# Cansat2019_1516_Container_v04.net
KiCad netlist of a schematic drawn in EAGLE
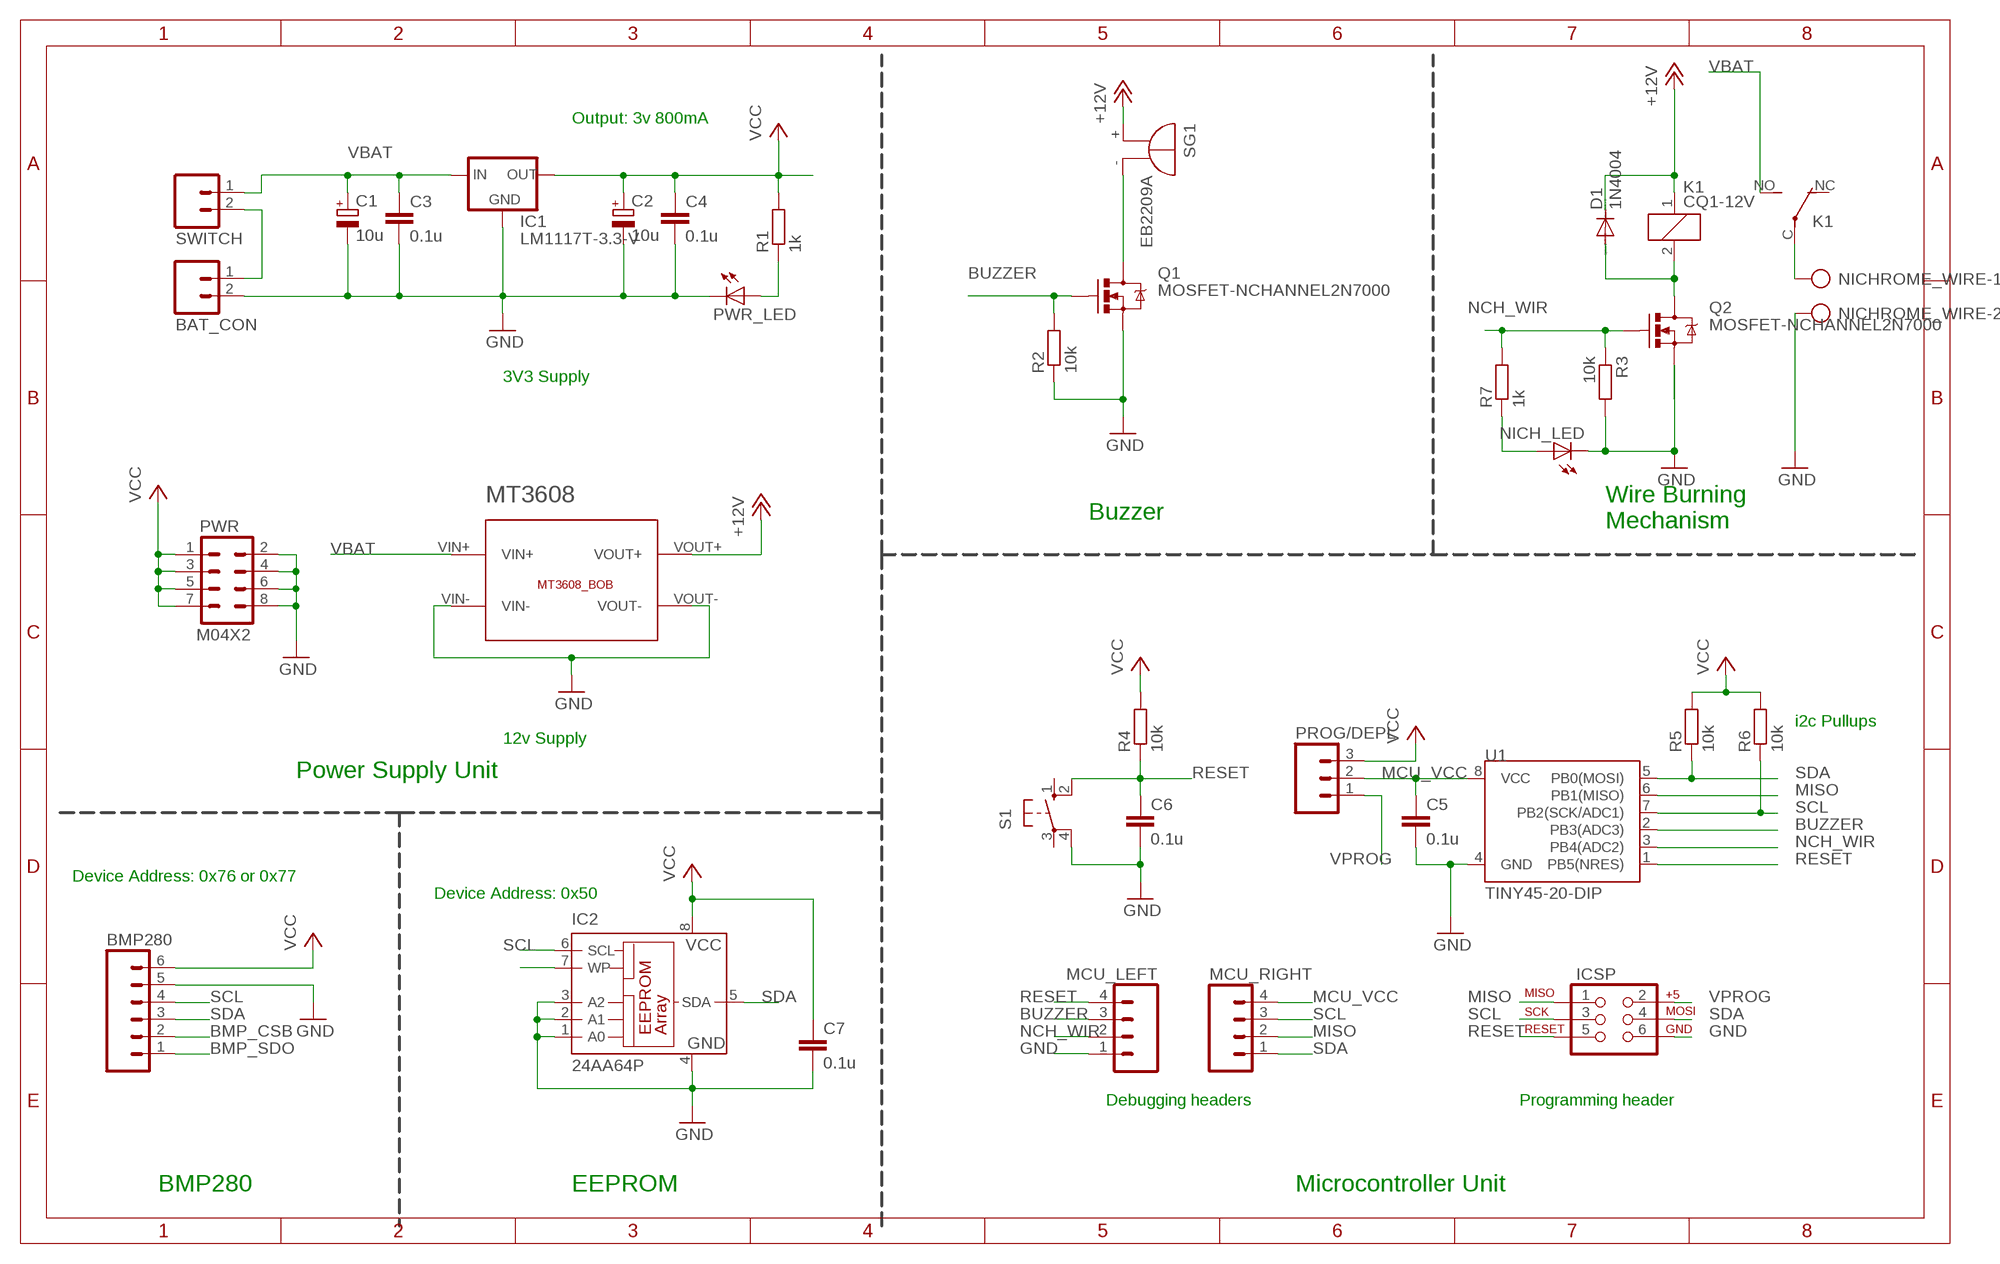
[diagram p0: schematic, sheet 1]

(export (version "E")
  (design (tool "Eeschema 10.0.6"))
  (components
    (comp (ref "BAT_CON")
      (value "M02")
      (footprint "eagle-import:02P")
      (libsource (lib "eagle-import") (part "M02"))
    )
    (comp (ref "BMP280")
      (value "M06")
      (footprint "eagle-import:06P")
      (libsource (lib "eagle-import") (part "M06"))
    )
    (comp (ref "C1")
      (value "10u")
      (footprint "eagle-import:E2,5-6")
      (libsource (lib "eagle-import") (part "CPOL-EUE2.5-6"))
    )
    (comp (ref "C2")
      (value "10u")
      (footprint "eagle-import:E2,5-6")
      (libsource (lib "eagle-import") (part "CPOL-EUE2.5-6"))
    )
    (comp (ref "C3")
      (value "0.1u")
      (footprint "eagle-import:C025-025X050")
      (libsource (lib "eagle-import") (part "C-EU025-025X050"))
    )
    (comp (ref "C4")
      (value "0.1u")
      (footprint "eagle-import:C025-025X050")
      (libsource (lib "eagle-import") (part "C-EU025-025X050"))
    )
    (comp (ref "C5")
      (value "0.1u")
      (footprint "eagle-import:C025-025X050")
      (libsource (lib "eagle-import") (part "C-EU025-025X050"))
    )
    (comp (ref "C6")
      (value "0.1u")
      (footprint "eagle-import:C025-025X050")
      (libsource (lib "eagle-import") (part "C-EU025-025X050"))
    )
    (comp (ref "C7")
      (value "0.1u")
      (footprint "eagle-import:C025-025X050")
      (libsource (lib "eagle-import") (part "C-EU025-025X050"))
    )
    (comp (ref "D1")
      (value "1N4004")
      (footprint "eagle-import:DO41-10")
      (libsource (lib "eagle-import") (part "1N4004"))
    )
    (comp (ref "IC1")
      (value "LM1117T-3.3-V")
      (footprint "eagle-import:TO220V")
      (libsource (lib "eagle-import") (part "LM1117T--V3.3"))
    )
    (comp (ref "IC2")
      (value "24AA64P")
      (footprint "eagle-import:DIL8")
      (fields (field (name "MF") "MICROCHIP") (field (name "MPN") "24AA64-I/P"))
      (libsource (lib "eagle-import") (part "24PAA64"))
    )
    (comp (ref "ICSP")
      (value "AVR_SPI_PRG_6NS")
      (footprint "eagle-import:2X3-NS")
      (libsource (lib "eagle-import") (part "AVR_SPI_PRG_6NS"))
    )
    (comp (ref "K1")
      (value "CQ1-12V")
      (footprint "eagle-import:CQ1")
      (libsource (lib "eagle-import") (part "CQ1-12V"))
    )
    (comp (ref "MCU_LEFT")
      (value "M04")
      (footprint "eagle-import:04P")
      (libsource (lib "eagle-import") (part "M04"))
    )
    (comp (ref "MCU_RIGHT")
      (value "M04")
      (footprint "eagle-import:04P")
      (libsource (lib "eagle-import") (part "M04"))
    )
    (comp (ref "MT3608")
      (value "MT3608_BOB")
      (footprint "eagle-import:MT3608_BOB")
      (libsource (lib "eagle-import") (part "MT3608_BOB"))
    )
    (comp (ref "NICHROME_WIRE")
      (value "AK500/2-H")
      (footprint "eagle-import:AK500_2-H")
      (libsource (lib "eagle-import") (part "AK500/2-H"))
    )
    (comp (ref "NICH_LED")
      (value "LED3MM")
      (footprint "eagle-import:LED3MM")
      (libsource (lib "eagle-import") (part "LED3MM"))
    )
    (comp (ref "PROG/DEPL")
      (value "M03PTH")
      (footprint "eagle-import:1X03")
      (libsource (lib "eagle-import") (part "M03PTH"))
    )
    (comp (ref "PWR")
      (value "M04X2")
      (footprint "eagle-import:2X4")
      (libsource (lib "eagle-import") (part "M04X2"))
    )
    (comp (ref "PWR_LED")
      (value "LED3MM")
      (footprint "eagle-import:LED3MM")
      (libsource (lib "eagle-import") (part "LED3MM"))
    )
    (comp (ref "Q1")
      (value "MOSFET-NCHANNEL2N7000")
      (footprint "eagle-import:TO-92")
      (libsource (lib "eagle-import") (part "MOSFET-NCHANNEL2N7000"))
    )
    (comp (ref "Q2")
      (value "MOSFET-NCHANNEL2N7000")
      (footprint "eagle-import:TO-92")
      (libsource (lib "eagle-import") (part "MOSFET-NCHANNEL2N7000"))
    )
    (comp (ref "R1")
      (value "1k")
      (footprint "eagle-import:0204_7")
      (libsource (lib "eagle-import") (part "R-EU_0204/7"))
    )
    (comp (ref "R2")
      (value "10k")
      (footprint "eagle-import:0204_7")
      (libsource (lib "eagle-import") (part "R-EU_0204/7"))
    )
    (comp (ref "R3")
      (value "10k")
      (footprint "eagle-import:0204_7")
      (libsource (lib "eagle-import") (part "R-EU_0204/7"))
    )
    (comp (ref "R4")
      (value "10k")
      (footprint "eagle-import:0204_7")
      (libsource (lib "eagle-import") (part "R-EU_0204/7"))
    )
    (comp (ref "R5")
      (value "10k")
      (footprint "eagle-import:0204_7")
      (libsource (lib "eagle-import") (part "R-EU_0204/7"))
    )
    (comp (ref "R6")
      (value "10k")
      (footprint "eagle-import:0204_7")
      (libsource (lib "eagle-import") (part "R-EU_0204/7"))
    )
    (comp (ref "R7")
      (value "1k")
      (footprint "eagle-import:0204_7")
      (libsource (lib "eagle-import") (part "R-EU_0204/7"))
    )
    (comp (ref "S1")
      (value "PUSH-BUTTON-6MM")
      (footprint "eagle-import:B3F-10XX")
      (libsource (lib "eagle-import") (part "PUSH-BUTTON-6MM"))
    )
    (comp (ref "SG1")
      (value "EB2209A")
      (footprint "eagle-import:EB2209A")
      (libsource (lib "eagle-import") (part "EB2209A"))
    )
    (comp (ref "SWITCH")
      (value "M02")
      (footprint "eagle-import:02P")
      (libsource (lib "eagle-import") (part "M02"))
    )
    (comp (ref "U1")
      (value "TINY45-20-DIP")
      (footprint "eagle-import:DIP08")
      (libsource (lib "eagle-import") (part "ATTINY45TINY45-20-DIP"))
    )
  )
  (nets
    (net (code "1") (name "+12V") (class "Default")
      (node (ref "D1") (pin "C") (pinfunction "C_C") (pintype "passive"))
      (node (ref "K1") (pin "1") (pinfunction "1_1") (pintype "passive"))
      (node (ref "MT3608") (pin "VOUT+") (pinfunction "VOUT+_VOUT+") (pintype "bidirectional"))
      (node (ref "SG1") (pin "+") (pinfunction "+_+") (pintype "passive"))
    )
    (net (code "2") (name "/BMP_CSB") (class "Default")
      (node (ref "BMP280") (pin "2") (pinfunction "2_2") (pintype "passive"))
    )
    (net (code "3") (name "/BMP_SDO") (class "Default")
      (node (ref "BMP280") (pin "1") (pinfunction "1_1") (pintype "passive"))
    )
    (net (code "4") (name "/BUZZER") (class "Default")
      (node (ref "MCU_LEFT") (pin "3") (pinfunction "3_3") (pintype "passive"))
      (node (ref "Q1") (pin "2") (pinfunction "G_2") (pintype "passive"))
      (node (ref "R2") (pin "2") (pinfunction "2_2") (pintype "passive"))
      (node (ref "U1") (pin "2") (pinfunction "PB3(ADC3)_2") (pintype "bidirectional"))
    )
    (net (code "5") (name "/MCU_VCC") (class "Default")
      (node (ref "C5") (pin "1") (pinfunction "1_1") (pintype "passive"))
      (node (ref "MCU_RIGHT") (pin "4") (pinfunction "4_4") (pintype "passive"))
      (node (ref "PROG/DEPL") (pin "2") (pinfunction "2_2") (pintype "passive"))
      (node (ref "U1") (pin "8") (pinfunction "VCC_8") (pintype "bidirectional"))
    )
    (net (code "6") (name "/MISO") (class "Default")
      (node (ref "ICSP") (pin "1") (pinfunction "1_1") (pintype "passive"))
      (node (ref "MCU_RIGHT") (pin "2") (pinfunction "2_2") (pintype "passive"))
      (node (ref "U1") (pin "6") (pinfunction "PB1(MISO)_6") (pintype "bidirectional"))
    )
    (net (code "7") (name "/NCH_WIR") (class "Default")
      (node (ref "MCU_LEFT") (pin "2") (pinfunction "2_2") (pintype "passive"))
      (node (ref "Q2") (pin "2") (pinfunction "G_2") (pintype "passive"))
      (node (ref "R3") (pin "1") (pinfunction "1_1") (pintype "passive"))
      (node (ref "R7") (pin "2") (pinfunction "2_2") (pintype "passive"))
      (node (ref "U1") (pin "3") (pinfunction "PB4(ADC2)_3") (pintype "bidirectional"))
    )
    (net (code "8") (name "/RESET") (class "Default")
      (node (ref "C6") (pin "1") (pinfunction "1_1") (pintype "passive"))
      (node (ref "ICSP") (pin "5") (pinfunction "5_5") (pintype "passive"))
      (node (ref "MCU_LEFT") (pin "4") (pinfunction "4_4") (pintype "passive"))
      (node (ref "R4") (pin "1") (pinfunction "1_1") (pintype "passive"))
      (node (ref "S1") (pin "2") (pinfunction "S1_2") (pintype "passive"))
      (node (ref "U1") (pin "1") (pinfunction "PB5(NRES)_1") (pintype "bidirectional"))
    )
    (net (code "9") (name "/SCL") (class "Default")
      (node (ref "BMP280") (pin "4") (pinfunction "4_4") (pintype "passive"))
      (node (ref "IC2") (pin "6") (pinfunction "SCL_6") (pintype "input"))
      (node (ref "ICSP") (pin "3") (pinfunction "3_3") (pintype "passive"))
      (node (ref "MCU_RIGHT") (pin "3") (pinfunction "3_3") (pintype "passive"))
      (node (ref "R6") (pin "1") (pinfunction "1_1") (pintype "passive"))
      (node (ref "U1") (pin "7") (pinfunction "PB2(SCK/ADC1)_7") (pintype "bidirectional"))
    )
    (net (code "10") (name "/SDA") (class "Default")
      (node (ref "BMP280") (pin "3") (pinfunction "3_3") (pintype "passive"))
      (node (ref "IC2") (pin "5") (pinfunction "SDA_5") (pintype "bidirectional"))
      (node (ref "ICSP") (pin "4") (pinfunction "4_4") (pintype "passive"))
      (node (ref "MCU_RIGHT") (pin "1") (pinfunction "1_1") (pintype "passive"))
      (node (ref "R5") (pin "1") (pinfunction "1_1") (pintype "passive"))
      (node (ref "U1") (pin "5") (pinfunction "PB0(MOSI)_5") (pintype "bidirectional"))
    )
    (net (code "11") (name "/VBAT") (class "Default")
      (node (ref "C1") (pin "+") (pinfunction "+_+") (pintype "passive"))
      (node (ref "C3") (pin "1") (pinfunction "1_1") (pintype "passive"))
      (node (ref "IC1") (pin "3") (pinfunction "IN_3") (pintype "input"))
      (node (ref "K1") (pin "NO") (pinfunction "S_NO") (pintype "passive"))
      (node (ref "MT3608") (pin "VIN+") (pinfunction "VIN+_VIN+") (pintype "bidirectional"))
      (node (ref "SWITCH") (pin "1") (pinfunction "1_1") (pintype "passive"))
    )
    (net (code "12") (name "/VPROG") (class "Default")
      (node (ref "ICSP") (pin "2") (pinfunction "2_2") (pintype "passive"))
      (node (ref "PROG/DEPL") (pin "1") (pinfunction "1_1") (pintype "passive"))
    )
    (net (code "13") (name "GND") (class "Default")
      (node (ref "BAT_CON") (pin "2") (pinfunction "2_2") (pintype "passive"))
      (node (ref "BMP280") (pin "5") (pinfunction "5_5") (pintype "passive"))
      (node (ref "C1") (pin "-") (pinfunction "-_-") (pintype "passive"))
      (node (ref "C2") (pin "-") (pinfunction "-_-") (pintype "passive"))
      (node (ref "C3") (pin "2") (pinfunction "2_2") (pintype "passive"))
      (node (ref "C4") (pin "2") (pinfunction "2_2") (pintype "passive"))
      (node (ref "C5") (pin "2") (pinfunction "2_2") (pintype "passive"))
      (node (ref "C6") (pin "2") (pinfunction "2_2") (pintype "passive"))
      (node (ref "C7") (pin "2") (pinfunction "2_2") (pintype "passive"))
      (node (ref "IC1") (pin "1") (pinfunction "GND_1") (pintype "input"))
      (node (ref "IC2") (pin "1") (pinfunction "A0_1") (pintype "input"))
      (node (ref "IC2") (pin "2") (pinfunction "A1_2") (pintype "input"))
      (node (ref "IC2") (pin "3") (pinfunction "A2_3") (pintype "input"))
      (node (ref "IC2") (pin "4") (pinfunction "GND_4") (pintype "power_in"))
      (node (ref "ICSP") (pin "6") (pinfunction "6_6") (pintype "passive"))
      (node (ref "MCU_LEFT") (pin "1") (pinfunction "1_1") (pintype "passive"))
      (node (ref "MT3608") (pin "VIN-") (pinfunction "VIN-_VIN-") (pintype "bidirectional"))
      (node (ref "MT3608") (pin "VOUT-") (pinfunction "VOUT-_VOUT-") (pintype "bidirectional"))
      (node (ref "NICHROME_WIRE") (pin "2") (pinfunction "KL_2") (pintype "passive"))
      (node (ref "NICH_LED") (pin "K") (pinfunction "C_K") (pintype "passive"))
      (node (ref "PWR") (pin "2") (pinfunction "2_2") (pintype "passive"))
      (node (ref "PWR") (pin "4") (pinfunction "4_4") (pintype "passive"))
      (node (ref "PWR") (pin "6") (pinfunction "6_6") (pintype "passive"))
      (node (ref "PWR") (pin "8") (pinfunction "8_8") (pintype "passive"))
      (node (ref "PWR_LED") (pin "K") (pinfunction "C_K") (pintype "passive"))
      (node (ref "Q1") (pin "1") (pinfunction "S_1") (pintype "passive"))
      (node (ref "Q2") (pin "1") (pinfunction "S_1") (pintype "passive"))
      (node (ref "R2") (pin "1") (pinfunction "1_1") (pintype "passive"))
      (node (ref "R3") (pin "2") (pinfunction "2_2") (pintype "passive"))
      (node (ref "S1") (pin "4") (pinfunction "P1_4") (pintype "passive"))
      (node (ref "U1") (pin "4") (pinfunction "GND_4") (pintype "bidirectional"))
    )
    (net (code "14") (name "Net-(BAT_CON-Pad1)") (class "Default")
      (node (ref "BAT_CON") (pin "1") (pinfunction "1_1") (pintype "passive"))
      (node (ref "SWITCH") (pin "2") (pinfunction "2_2") (pintype "passive"))
    )
    (net (code "15") (name "Net-(K1B-P)") (class "Default")
      (node (ref "K1") (pin "C") (pinfunction "P_C") (pintype "passive"))
      (node (ref "NICHROME_WIRE") (pin "1") (pinfunction "KL_1") (pintype "passive"))
    )
    (net (code "16") (name "Net-(NICH_LED-PadA)") (class "Default")
      (node (ref "NICH_LED") (pin "A") (pinfunction "A_A") (pintype "passive"))
      (node (ref "R7") (pin "1") (pinfunction "1_1") (pintype "passive"))
    )
    (net (code "17") (name "Net-(PWR_LED-PadA)") (class "Default")
      (node (ref "PWR_LED") (pin "A") (pinfunction "A_A") (pintype "passive"))
      (node (ref "R1") (pin "1") (pinfunction "1_1") (pintype "passive"))
    )
    (net (code "18") (name "Net-(Q1-D)") (class "Default")
      (node (ref "Q1") (pin "3") (pinfunction "D_3") (pintype "passive"))
      (node (ref "SG1") (pin "-") (pinfunction "-_-") (pintype "passive"))
    )
    (net (code "19") (name "Net-(Q2-D)") (class "Default")
      (node (ref "D1") (pin "A") (pinfunction "A_A") (pintype "passive"))
      (node (ref "K1") (pin "2") (pinfunction "2_2") (pintype "passive"))
      (node (ref "Q2") (pin "3") (pinfunction "D_3") (pintype "passive"))
    )
    (net (code "20") (name "VCC") (class "Default")
      (node (ref "BMP280") (pin "6") (pinfunction "6_6") (pintype "passive"))
      (node (ref "C2") (pin "+") (pinfunction "+_+") (pintype "passive"))
      (node (ref "C4") (pin "1") (pinfunction "1_1") (pintype "passive"))
      (node (ref "C7") (pin "1") (pinfunction "1_1") (pintype "passive"))
      (node (ref "IC1") (pin "2") (pinfunction "OUT_2") (pintype "passive"))
      (node (ref "IC2") (pin "8") (pinfunction "VCC_8") (pintype "power_in"))
      (node (ref "PROG/DEPL") (pin "3") (pinfunction "3_3") (pintype "passive"))
      (node (ref "PWR") (pin "1") (pinfunction "1_1") (pintype "passive"))
      (node (ref "PWR") (pin "3") (pinfunction "3_3") (pintype "passive"))
      (node (ref "PWR") (pin "5") (pinfunction "5_5") (pintype "passive"))
      (node (ref "PWR") (pin "7") (pinfunction "7_7") (pintype "passive"))
      (node (ref "R1") (pin "2") (pinfunction "2_2") (pintype "passive"))
      (node (ref "R4") (pin "2") (pinfunction "2_2") (pintype "passive"))
      (node (ref "R5") (pin "2") (pinfunction "2_2") (pintype "passive"))
      (node (ref "R6") (pin "2") (pinfunction "2_2") (pintype "passive"))
    )
    (net (code "21") (name "unconnected-(IC2-WP-Pad7)") (class "Default")
      (node (ref "IC2") (pin "7") (pinfunction "WP_7") (pintype "input"))
    )
    (net (code "22") (name "unconnected-(K1B-O-PadNC)") (class "Default")
      (node (ref "K1") (pin "NC") (pinfunction "O_NC") (pintype "passive"))
    )
    (net (code "23") (name "unconnected-(S1-P-Pad3)") (class "Default")
      (node (ref "S1") (pin "3") (pinfunction "P_3") (pintype "passive"))
    )
    (net (code "24") (name "unconnected-(S1-S-Pad1)") (class "Default")
      (node (ref "S1") (pin "1") (pinfunction "S_1") (pintype "passive"))
    )
  )
)
